# scheme.net
KiCad netlist of a schematic drawn in EAGLE
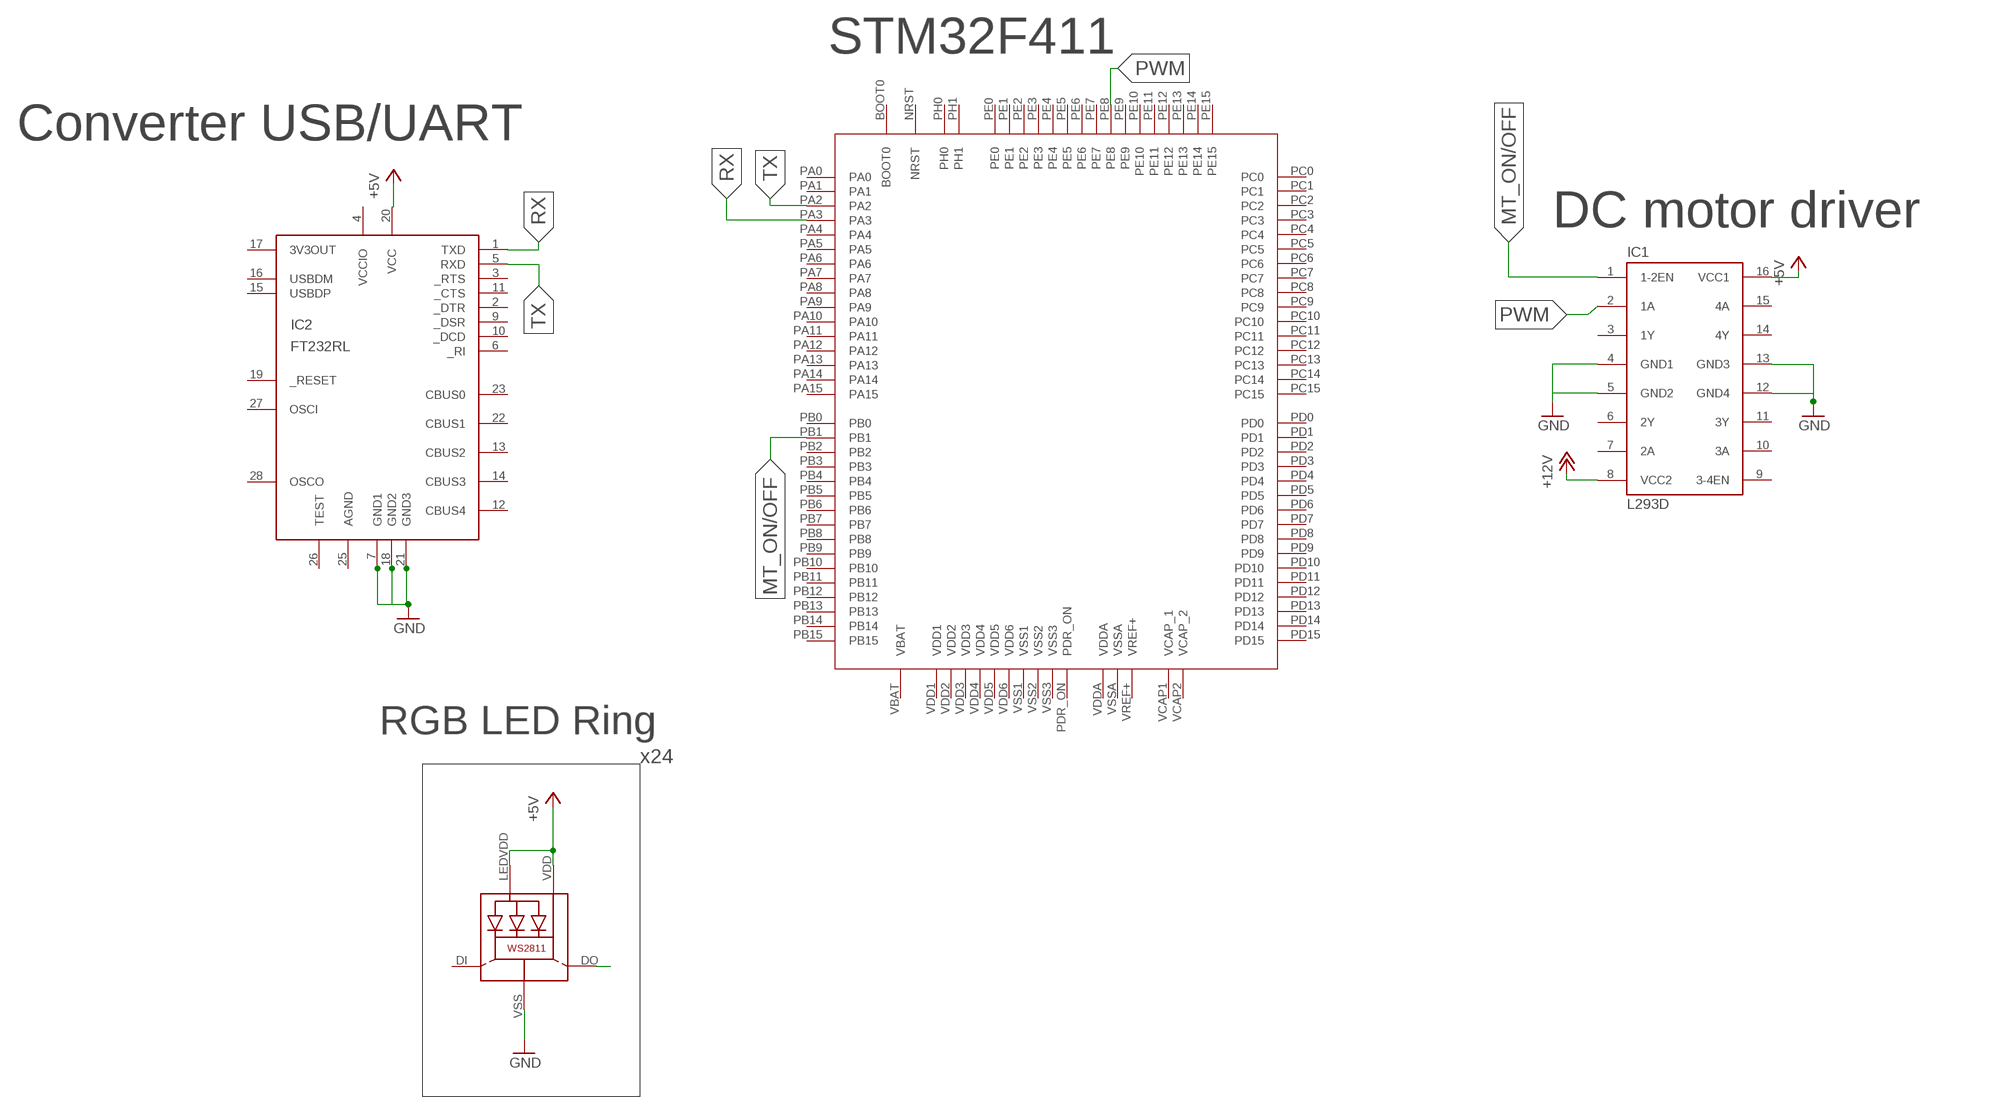
[diagram p0: schematic, sheet 1]

(export (version "E")
  (design (tool "Eeschema 10.0.6"))
  (components
    (comp (ref "IC1")
      (value "L293D")
      (footprint "eagle-import:DIL16")
      (libsource (lib "eagle-import") (part "L293D"))
    )
    (comp (ref "IC2")
      (value "FT232RL")
      (footprint "eagle-import:SSOP28DB")
      (libsource (lib "eagle-import") (part "FT232RL"))
    )
    (comp (ref "LED12")
      (value "WS28115050")
      (footprint "eagle-import:WS28115050")
      (libsource (lib "eagle-import") (part "WS28115050"))
    )
    (comp (ref "U$2")
      (value "STM32F4V_100PIN_GENERIC")
      (footprint "eagle-import:LQFP100")
      (libsource (lib "eagle-import") (part "STM32F4V_100PIN_GENERIC"))
    )
  )
  (nets
    (net (code "1") (name "+5V") (class "Default")
      (node (ref "IC1") (pin "16") (pinfunction "VCC1_16") (pintype "power_in"))
      (node (ref "IC2") (pin "20") (pinfunction "VCC_20") (pintype "power_in"))
      (node (ref "LED12") (pin "LEDVDD") (pinfunction "LEDVDD_LEDVDD") (pintype "power_in"))
      (node (ref "LED12") (pin "VDD") (pinfunction "VDD_VDD") (pintype "power_in"))
    )
    (net (code "2") (name "+12V") (class "Default")
      (node (ref "IC1") (pin "8") (pinfunction "VCC2_8") (pintype "power_in"))
    )
    (net (code "3") (name "/AGND") (class "Default")
      (node (ref "IC2") (pin "25") (pinfunction "AGND_25") (pintype "power_in"))
    )
    (net (code "4") (name "/VCCIO") (class "Default")
      (node (ref "IC2") (pin "4") (pinfunction "VCCIO_4") (pintype "power_in"))
    )
    (net (code "5") (name "GND") (class "Default")
      (node (ref "IC1") (pin "12") (pinfunction "GND4_12") (pintype "power_in"))
      (node (ref "IC1") (pin "13") (pinfunction "GND3_13") (pintype "power_in"))
      (node (ref "IC1") (pin "4") (pinfunction "GND1_4") (pintype "power_in"))
      (node (ref "IC1") (pin "5") (pinfunction "GND2_5") (pintype "power_in"))
      (node (ref "IC2") (pin "18") (pinfunction "GND2_18") (pintype "power_in"))
      (node (ref "IC2") (pin "21") (pinfunction "GND3_21") (pintype "power_in"))
      (node (ref "IC2") (pin "7") (pinfunction "GND1_7") (pintype "power_in"))
      (node (ref "LED12") (pin "VSS") (pinfunction "GND_VSS") (pintype "power_in"))
    )
    (net (code "6") (name "MT_ON{slash}OFF") (class "Default")
      (node (ref "IC1") (pin "1") (pinfunction "1-2EN_1") (pintype "input"))
      (node (ref "U$2") (pin "PB1") (pinfunction "PB1_PB1") (pintype "bidirectional"))
    )
    (net (code "7") (name "PWM") (class "Default")
      (node (ref "IC1") (pin "2") (pinfunction "1A_2") (pintype "input"))
      (node (ref "U$2") (pin "PE8") (pinfunction "PE8_PE8") (pintype "bidirectional"))
    )
    (net (code "8") (name "RX") (class "Default")
      (node (ref "IC2") (pin "1") (pinfunction "TXD_1") (pintype "output"))
      (node (ref "U$2") (pin "PA3") (pinfunction "PA3_PA3") (pintype "bidirectional"))
    )
    (net (code "9") (name "TX") (class "Default")
      (node (ref "IC2") (pin "5") (pinfunction "RXD_5") (pintype "input"))
      (node (ref "U$2") (pin "PA2") (pinfunction "PA2_PA2") (pintype "bidirectional"))
    )
    (net (code "10") (name "unconnected-(IC1-1Y-Pad3)") (class "Default")
      (node (ref "IC1") (pin "3") (pinfunction "1Y_3") (pintype "output"))
    )
    (net (code "11") (name "unconnected-(IC1-2A-Pad7)") (class "Default")
      (node (ref "IC1") (pin "7") (pinfunction "2A_7") (pintype "input"))
    )
    (net (code "12") (name "unconnected-(IC1-2Y-Pad6)") (class "Default")
      (node (ref "IC1") (pin "6") (pinfunction "2Y_6") (pintype "output"))
    )
    (net (code "13") (name "unconnected-(IC1-3-4EN-Pad9)") (class "Default")
      (node (ref "IC1") (pin "9") (pinfunction "3-4EN_9") (pintype "input"))
    )
    (net (code "14") (name "unconnected-(IC1-3A-Pad10)") (class "Default")
      (node (ref "IC1") (pin "10") (pinfunction "3A_10") (pintype "input"))
    )
    (net (code "15") (name "unconnected-(IC1-3Y-Pad11)") (class "Default")
      (node (ref "IC1") (pin "11") (pinfunction "3Y_11") (pintype "output"))
    )
    (net (code "16") (name "unconnected-(IC1-4A-Pad15)") (class "Default")
      (node (ref "IC1") (pin "15") (pinfunction "4A_15") (pintype "input"))
    )
    (net (code "17") (name "unconnected-(IC1-4Y-Pad14)") (class "Default")
      (node (ref "IC1") (pin "14") (pinfunction "4Y_14") (pintype "output"))
    )
    (net (code "18") (name "unconnected-(IC2-3V3OUT-Pad17)") (class "Default")
      (node (ref "IC2") (pin "17") (pinfunction "3V3OUT_17") (pintype "output"))
    )
    (net (code "19") (name "unconnected-(IC2-CBUS0-Pad23)") (class "Default")
      (node (ref "IC2") (pin "23") (pinfunction "CBUS0_23") (pintype "bidirectional"))
    )
    (net (code "20") (name "unconnected-(IC2-CBUS1-Pad22)") (class "Default")
      (node (ref "IC2") (pin "22") (pinfunction "CBUS1_22") (pintype "bidirectional"))
    )
    (net (code "21") (name "unconnected-(IC2-CBUS2-Pad13)") (class "Default")
      (node (ref "IC2") (pin "13") (pinfunction "CBUS2_13") (pintype "bidirectional"))
    )
    (net (code "22") (name "unconnected-(IC2-CBUS3-Pad14)") (class "Default")
      (node (ref "IC2") (pin "14") (pinfunction "CBUS3_14") (pintype "bidirectional"))
    )
    (net (code "23") (name "unconnected-(IC2-CBUS4-Pad12)") (class "Default")
      (node (ref "IC2") (pin "12") (pinfunction "CBUS4_12") (pintype "bidirectional"))
    )
    (net (code "24") (name "unconnected-(IC2-OSCI-Pad27)") (class "Default")
      (node (ref "IC2") (pin "27") (pinfunction "OSCI_27") (pintype "input"))
    )
    (net (code "25") (name "unconnected-(IC2-OSCO-Pad28)") (class "Default")
      (node (ref "IC2") (pin "28") (pinfunction "OSCO_28") (pintype "output"))
    )
    (net (code "26") (name "unconnected-(IC2-TEST-Pad26)") (class "Default")
      (node (ref "IC2") (pin "26") (pinfunction "TEST_26") (pintype "input"))
    )
    (net (code "27") (name "unconnected-(IC2-USBDM-Pad16)") (class "Default")
      (node (ref "IC2") (pin "16") (pinfunction "USBDM_16") (pintype "bidirectional"))
    )
    (net (code "28") (name "unconnected-(IC2-USBDP-Pad15)") (class "Default")
      (node (ref "IC2") (pin "15") (pinfunction "USBDP_15") (pintype "bidirectional"))
    )
    (net (code "29") (name "unconnected-(IC2-_CTS-Pad11)") (class "Default")
      (node (ref "IC2") (pin "11") (pinfunction "_CTS_11") (pintype "input"))
    )
    (net (code "30") (name "unconnected-(IC2-_DCD-Pad10)") (class "Default")
      (node (ref "IC2") (pin "10") (pinfunction "_DCD_10") (pintype "input"))
    )
    (net (code "31") (name "unconnected-(IC2-_DSR-Pad9)") (class "Default")
      (node (ref "IC2") (pin "9") (pinfunction "_DSR_9") (pintype "input"))
    )
    (net (code "32") (name "unconnected-(IC2-_DTR-Pad2)") (class "Default")
      (node (ref "IC2") (pin "2") (pinfunction "_DTR_2") (pintype "output"))
    )
    (net (code "33") (name "unconnected-(IC2-_RESET-Pad19)") (class "Default")
      (node (ref "IC2") (pin "19") (pinfunction "_RESET_19") (pintype "input"))
    )
    (net (code "34") (name "unconnected-(IC2-_RI-Pad6)") (class "Default")
      (node (ref "IC2") (pin "6") (pinfunction "_RI_6") (pintype "input"))
    )
    (net (code "35") (name "unconnected-(IC2-_RTS-Pad3)") (class "Default")
      (node (ref "IC2") (pin "3") (pinfunction "_RTS_3") (pintype "output"))
    )
    (net (code "36") (name "unconnected-(LED12-PadDI)") (class "Default")
      (node (ref "LED12") (pin "DI") (pinfunction "DI_DI") (pintype "input"))
    )
    (net (code "37") (name "unconnected-(LED12-PadDO)") (class "Default")
      (node (ref "LED12") (pin "DO") (pinfunction "DO_DO") (pintype "output"))
    )
    (net (code "38") (name "unconnected-(U$2-PadBOOT0)") (class "Default")
      (node (ref "U$2") (pin "BOOT0") (pinfunction "BOOT0_BOOT0") (pintype "bidirectional"))
    )
    (net (code "39") (name "unconnected-(U$2-PadNRST)") (class "Default")
      (node (ref "U$2") (pin "NRST") (pinfunction "NRST_NRST") (pintype "bidirectional"))
    )
    (net (code "40") (name "unconnected-(U$2-PadPA0)") (class "Default")
      (node (ref "U$2") (pin "PA0") (pinfunction "PA0_PA0") (pintype "bidirectional"))
    )
    (net (code "41") (name "unconnected-(U$2-PadPA1)") (class "Default")
      (node (ref "U$2") (pin "PA1") (pinfunction "PA1_PA1") (pintype "bidirectional"))
    )
    (net (code "42") (name "unconnected-(U$2-PadPA4)") (class "Default")
      (node (ref "U$2") (pin "PA4") (pinfunction "PA4_PA4") (pintype "bidirectional"))
    )
    (net (code "43") (name "unconnected-(U$2-PadPA5)") (class "Default")
      (node (ref "U$2") (pin "PA5") (pinfunction "PA5_PA5") (pintype "bidirectional"))
    )
    (net (code "44") (name "unconnected-(U$2-PadPA6)") (class "Default")
      (node (ref "U$2") (pin "PA6") (pinfunction "PA6_PA6") (pintype "bidirectional"))
    )
    (net (code "45") (name "unconnected-(U$2-PadPA7)") (class "Default")
      (node (ref "U$2") (pin "PA7") (pinfunction "PA7_PA7") (pintype "bidirectional"))
    )
    (net (code "46") (name "unconnected-(U$2-PadPA8)") (class "Default")
      (node (ref "U$2") (pin "PA8") (pinfunction "PA8_PA8") (pintype "bidirectional"))
    )
    (net (code "47") (name "unconnected-(U$2-PadPA9)") (class "Default")
      (node (ref "U$2") (pin "PA9") (pinfunction "PA9_PA9") (pintype "bidirectional"))
    )
    (net (code "48") (name "unconnected-(U$2-PadPA10)") (class "Default")
      (node (ref "U$2") (pin "PA10") (pinfunction "PA10_PA10") (pintype "bidirectional"))
    )
    (net (code "49") (name "unconnected-(U$2-PadPA11)") (class "Default")
      (node (ref "U$2") (pin "PA11") (pinfunction "PA11_PA11") (pintype "bidirectional"))
    )
    (net (code "50") (name "unconnected-(U$2-PadPA12)") (class "Default")
      (node (ref "U$2") (pin "PA12") (pinfunction "PA12_PA12") (pintype "bidirectional"))
    )
    (net (code "51") (name "unconnected-(U$2-PadPA13)") (class "Default")
      (node (ref "U$2") (pin "PA13") (pinfunction "PA13_PA13") (pintype "bidirectional"))
    )
    (net (code "52") (name "unconnected-(U$2-PadPA14)") (class "Default")
      (node (ref "U$2") (pin "PA14") (pinfunction "PA14_PA14") (pintype "bidirectional"))
    )
    (net (code "53") (name "unconnected-(U$2-PadPA15)") (class "Default")
      (node (ref "U$2") (pin "PA15") (pinfunction "PA15_PA15") (pintype "bidirectional"))
    )
    (net (code "54") (name "unconnected-(U$2-PadPB0)") (class "Default")
      (node (ref "U$2") (pin "PB0") (pinfunction "PB0_PB0") (pintype "bidirectional"))
    )
    (net (code "55") (name "unconnected-(U$2-PadPB2)") (class "Default")
      (node (ref "U$2") (pin "PB2") (pinfunction "PB2_PB2") (pintype "bidirectional"))
    )
    (net (code "56") (name "unconnected-(U$2-PadPB3)") (class "Default")
      (node (ref "U$2") (pin "PB3") (pinfunction "PB3_PB3") (pintype "bidirectional"))
    )
    (net (code "57") (name "unconnected-(U$2-PadPB4)") (class "Default")
      (node (ref "U$2") (pin "PB4") (pinfunction "PB4_PB4") (pintype "bidirectional"))
    )
    (net (code "58") (name "unconnected-(U$2-PadPB5)") (class "Default")
      (node (ref "U$2") (pin "PB5") (pinfunction "PB5_PB5") (pintype "bidirectional"))
    )
    (net (code "59") (name "unconnected-(U$2-PadPB6)") (class "Default")
      (node (ref "U$2") (pin "PB6") (pinfunction "PB6_PB6") (pintype "bidirectional"))
    )
    (net (code "60") (name "unconnected-(U$2-PadPB7)") (class "Default")
      (node (ref "U$2") (pin "PB7") (pinfunction "PB7_PB7") (pintype "bidirectional"))
    )
    (net (code "61") (name "unconnected-(U$2-PadPB8)") (class "Default")
      (node (ref "U$2") (pin "PB8") (pinfunction "PB8_PB8") (pintype "bidirectional"))
    )
    (net (code "62") (name "unconnected-(U$2-PadPB9)") (class "Default")
      (node (ref "U$2") (pin "PB9") (pinfunction "PB9_PB9") (pintype "bidirectional"))
    )
    (net (code "63") (name "unconnected-(U$2-PadPB10)") (class "Default")
      (node (ref "U$2") (pin "PB10") (pinfunction "PB10_PB10") (pintype "bidirectional"))
    )
    (net (code "64") (name "unconnected-(U$2-PadPB11)") (class "Default")
      (node (ref "U$2") (pin "PB11") (pinfunction "PB11_PB11") (pintype "bidirectional"))
    )
    (net (code "65") (name "unconnected-(U$2-PadPB12)") (class "Default")
      (node (ref "U$2") (pin "PB12") (pinfunction "PB12_PB12") (pintype "bidirectional"))
    )
    (net (code "66") (name "unconnected-(U$2-PadPB13)") (class "Default")
      (node (ref "U$2") (pin "PB13") (pinfunction "PB13_PB13") (pintype "bidirectional"))
    )
    (net (code "67") (name "unconnected-(U$2-PadPB14)") (class "Default")
      (node (ref "U$2") (pin "PB14") (pinfunction "PB14_PB14") (pintype "bidirectional"))
    )
    (net (code "68") (name "unconnected-(U$2-PadPB15)") (class "Default")
      (node (ref "U$2") (pin "PB15") (pinfunction "PB15_PB15") (pintype "bidirectional"))
    )
    (net (code "69") (name "unconnected-(U$2-PadPC0)") (class "Default")
      (node (ref "U$2") (pin "PC0") (pinfunction "PC0_PC0") (pintype "bidirectional"))
    )
    (net (code "70") (name "unconnected-(U$2-PadPC1)") (class "Default")
      (node (ref "U$2") (pin "PC1") (pinfunction "PC1_PC1") (pintype "bidirectional"))
    )
    (net (code "71") (name "unconnected-(U$2-PadPC2)") (class "Default")
      (node (ref "U$2") (pin "PC2") (pinfunction "PC2_PC2") (pintype "bidirectional"))
    )
    (net (code "72") (name "unconnected-(U$2-PadPC3)") (class "Default")
      (node (ref "U$2") (pin "PC3") (pinfunction "PC3_PC3") (pintype "bidirectional"))
    )
    (net (code "73") (name "unconnected-(U$2-PadPC4)") (class "Default")
      (node (ref "U$2") (pin "PC4") (pinfunction "PC4_PC4") (pintype "bidirectional"))
    )
    (net (code "74") (name "unconnected-(U$2-PadPC5)") (class "Default")
      (node (ref "U$2") (pin "PC5") (pinfunction "PC5_PC5") (pintype "bidirectional"))
    )
    (net (code "75") (name "unconnected-(U$2-PadPC6)") (class "Default")
      (node (ref "U$2") (pin "PC6") (pinfunction "PC6_PC6") (pintype "bidirectional"))
    )
    (net (code "76") (name "unconnected-(U$2-PadPC7)") (class "Default")
      (node (ref "U$2") (pin "PC7") (pinfunction "PC7_PC7") (pintype "bidirectional"))
    )
    (net (code "77") (name "unconnected-(U$2-PadPC8)") (class "Default")
      (node (ref "U$2") (pin "PC8") (pinfunction "PC8_PC8") (pintype "bidirectional"))
    )
    (net (code "78") (name "unconnected-(U$2-PadPC9)") (class "Default")
      (node (ref "U$2") (pin "PC9") (pinfunction "PC9_PC9") (pintype "bidirectional"))
    )
    (net (code "79") (name "unconnected-(U$2-PadPC10)") (class "Default")
      (node (ref "U$2") (pin "PC10") (pinfunction "PC10_PC10") (pintype "bidirectional"))
    )
    (net (code "80") (name "unconnected-(U$2-PadPC11)") (class "Default")
      (node (ref "U$2") (pin "PC11") (pinfunction "PC11_PC11") (pintype "bidirectional"))
    )
    (net (code "81") (name "unconnected-(U$2-PadPC12)") (class "Default")
      (node (ref "U$2") (pin "PC12") (pinfunction "PC12_PC12") (pintype "bidirectional"))
    )
    (net (code "82") (name "unconnected-(U$2-PadPC13)") (class "Default")
      (node (ref "U$2") (pin "PC13") (pinfunction "PC13_PC13") (pintype "bidirectional"))
    )
    (net (code "83") (name "unconnected-(U$2-PadPC14)") (class "Default")
      (node (ref "U$2") (pin "PC14") (pinfunction "PC14_PC14") (pintype "bidirectional"))
    )
    (net (code "84") (name "unconnected-(U$2-PadPC15)") (class "Default")
      (node (ref "U$2") (pin "PC15") (pinfunction "PC15_PC15") (pintype "bidirectional"))
    )
    (net (code "85") (name "unconnected-(U$2-PadPD0)") (class "Default")
      (node (ref "U$2") (pin "PD0") (pinfunction "PD0_PD0") (pintype "bidirectional"))
    )
    (net (code "86") (name "unconnected-(U$2-PadPD1)") (class "Default")
      (node (ref "U$2") (pin "PD1") (pinfunction "PD1_PD1") (pintype "bidirectional"))
    )
    (net (code "87") (name "unconnected-(U$2-PadPD2)") (class "Default")
      (node (ref "U$2") (pin "PD2") (pinfunction "PD2_PD2") (pintype "bidirectional"))
    )
    (net (code "88") (name "unconnected-(U$2-PadPD3)") (class "Default")
      (node (ref "U$2") (pin "PD3") (pinfunction "PD3_PD3") (pintype "bidirectional"))
    )
    (net (code "89") (name "unconnected-(U$2-PadPD4)") (class "Default")
      (node (ref "U$2") (pin "PD4") (pinfunction "PD4_PD4") (pintype "bidirectional"))
    )
    (net (code "90") (name "unconnected-(U$2-PadPD5)") (class "Default")
      (node (ref "U$2") (pin "PD5") (pinfunction "PD5_PD5") (pintype "bidirectional"))
    )
    (net (code "91") (name "unconnected-(U$2-PadPD6)") (class "Default")
      (node (ref "U$2") (pin "PD6") (pinfunction "PD6_PD6") (pintype "bidirectional"))
    )
    (net (code "92") (name "unconnected-(U$2-PadPD7)") (class "Default")
      (node (ref "U$2") (pin "PD7") (pinfunction "PD7_PD7") (pintype "bidirectional"))
    )
    (net (code "93") (name "unconnected-(U$2-PadPD8)") (class "Default")
      (node (ref "U$2") (pin "PD8") (pinfunction "PD8_PD8") (pintype "bidirectional"))
    )
    (net (code "94") (name "unconnected-(U$2-PadPD9)") (class "Default")
      (node (ref "U$2") (pin "PD9") (pinfunction "PD9_PD9") (pintype "bidirectional"))
    )
    (net (code "95") (name "unconnected-(U$2-PadPD10)") (class "Default")
      (node (ref "U$2") (pin "PD10") (pinfunction "PD10_PD10") (pintype "bidirectional"))
    )
    (net (code "96") (name "unconnected-(U$2-PadPD11)") (class "Default")
      (node (ref "U$2") (pin "PD11") (pinfunction "PD11_PD11") (pintype "bidirectional"))
    )
    (net (code "97") (name "unconnected-(U$2-PadPD12)") (class "Default")
      (node (ref "U$2") (pin "PD12") (pinfunction "PD12_PD12") (pintype "bidirectional"))
    )
    (net (code "98") (name "unconnected-(U$2-PadPD13)") (class "Default")
      (node (ref "U$2") (pin "PD13") (pinfunction "PD13_PD13") (pintype "bidirectional"))
    )
    (net (code "99") (name "unconnected-(U$2-PadPD14)") (class "Default")
      (node (ref "U$2") (pin "PD14") (pinfunction "PD14_PD14") (pintype "bidirectional"))
    )
    (net (code "100") (name "unconnected-(U$2-PadPD15)") (class "Default")
      (node (ref "U$2") (pin "PD15") (pinfunction "PD15_PD15") (pintype "bidirectional"))
    )
    (net (code "101") (name "unconnected-(U$2-PadPDR_ON)") (class "Default")
      (node (ref "U$2") (pin "PDR_ON") (pinfunction "PDR_ON_PDR_ON") (pintype "bidirectional"))
    )
    (net (code "102") (name "unconnected-(U$2-PadPE0)") (class "Default")
      (node (ref "U$2") (pin "PE0") (pinfunction "PE0_PE0") (pintype "bidirectional"))
    )
    (net (code "103") (name "unconnected-(U$2-PadPE1)") (class "Default")
      (node (ref "U$2") (pin "PE1") (pinfunction "PE1_PE1") (pintype "bidirectional"))
    )
    (net (code "104") (name "unconnected-(U$2-PadPE2)") (class "Default")
      (node (ref "U$2") (pin "PE2") (pinfunction "PE2_PE2") (pintype "bidirectional"))
    )
    (net (code "105") (name "unconnected-(U$2-PadPE3)") (class "Default")
      (node (ref "U$2") (pin "PE3") (pinfunction "PE3_PE3") (pintype "bidirectional"))
    )
    (net (code "106") (name "unconnected-(U$2-PadPE4)") (class "Default")
      (node (ref "U$2") (pin "PE4") (pinfunction "PE4_PE4") (pintype "bidirectional"))
    )
    (net (code "107") (name "unconnected-(U$2-PadPE5)") (class "Default")
      (node (ref "U$2") (pin "PE5") (pinfunction "PE5_PE5") (pintype "bidirectional"))
    )
    (net (code "108") (name "unconnected-(U$2-PadPE6)") (class "Default")
      (node (ref "U$2") (pin "PE6") (pinfunction "PE6_PE6") (pintype "bidirectional"))
    )
    (net (code "109") (name "unconnected-(U$2-PadPE7)") (class "Default")
      (node (ref "U$2") (pin "PE7") (pinfunction "PE7_PE7") (pintype "bidirectional"))
    )
    (net (code "110") (name "unconnected-(U$2-PadPE9)") (class "Default")
      (node (ref "U$2") (pin "PE9") (pinfunction "PE9_PE9") (pintype "bidirectional"))
    )
    (net (code "111") (name "unconnected-(U$2-PadPE10)") (class "Default")
      (node (ref "U$2") (pin "PE10") (pinfunction "PE10_PE10") (pintype "bidirectional"))
    )
    (net (code "112") (name "unconnected-(U$2-PadPE11)") (class "Default")
      (node (ref "U$2") (pin "PE11") (pinfunction "PE11_PE11") (pintype "bidirectional"))
    )
    (net (code "113") (name "unconnected-(U$2-PadPE12)") (class "Default")
      (node (ref "U$2") (pin "PE12") (pinfunction "PE12_PE12") (pintype "bidirectional"))
    )
    (net (code "114") (name "unconnected-(U$2-PadPE13)") (class "Default")
      (node (ref "U$2") (pin "PE13") (pinfunction "PE13_PE13") (pintype "bidirectional"))
    )
    (net (code "115") (name "unconnected-(U$2-PadPE14)") (class "Default")
      (node (ref "U$2") (pin "PE14") (pinfunction "PE14_PE14") (pintype "bidirectional"))
    )
    (net (code "116") (name "unconnected-(U$2-PadPE15)") (class "Default")
      (node (ref "U$2") (pin "PE15") (pinfunction "PE15_PE15") (pintype "bidirectional"))
    )
    (net (code "117") (name "unconnected-(U$2-PadPH0)") (class "Default")
      (node (ref "U$2") (pin "PH0") (pinfunction "PH0_PH0") (pintype "bidirectional"))
    )
    (net (code "118") (name "unconnected-(U$2-PadPH1)") (class "Default")
      (node (ref "U$2") (pin "PH1") (pinfunction "PH1_PH1") (pintype "bidirectional"))
    )
    (net (code "119") (name "unconnected-(U$2-PadVBAT)") (class "Default")
      (node (ref "U$2") (pin "VBAT") (pinfunction "VBAT_VBAT") (pintype "bidirectional"))
    )
    (net (code "120") (name "unconnected-(U$2-PadVDD1)") (class "Default")
      (node (ref "U$2") (pin "VDD1") (pinfunction "VDD1_VDD1") (pintype "bidirectional"))
    )
    (net (code "121") (name "unconnected-(U$2-PadVDD2)") (class "Default")
      (node (ref "U$2") (pin "VDD2") (pinfunction "VDD2_VDD2") (pintype "bidirectional"))
    )
    (net (code "122") (name "unconnected-(U$2-PadVDD3)") (class "Default")
      (node (ref "U$2") (pin "VDD3") (pinfunction "VDD3_VDD3") (pintype "bidirectional"))
    )
    (net (code "123") (name "unconnected-(U$2-PadVDD4)") (class "Default")
      (node (ref "U$2") (pin "VDD4") (pinfunction "VDD4_VDD4") (pintype "bidirectional"))
    )
    (net (code "124") (name "unconnected-(U$2-PadVDD5)") (class "Default")
      (node (ref "U$2") (pin "VDD5") (pinfunction "VDD5_VDD5") (pintype "bidirectional"))
    )
    (net (code "125") (name "unconnected-(U$2-PadVDD6)") (class "Default")
      (node (ref "U$2") (pin "VDD6") (pinfunction "VDD6_VDD6") (pintype "bidirectional"))
    )
    (net (code "126") (name "unconnected-(U$2-PadVDDA)") (class "Default")
      (node (ref "U$2") (pin "VDDA") (pinfunction "VDDA_VDDA") (pintype "bidirectional"))
    )
    (net (code "127") (name "unconnected-(U$2-PadVREF+)") (class "Default")
      (node (ref "U$2") (pin "VREF+") (pinfunction "VREF+_VREF+") (pintype "bidirectional"))
    )
    (net (code "128") (name "unconnected-(U$2-PadVSS1)") (class "Default")
      (node (ref "U$2") (pin "VSS1") (pinfunction "VSS1_VSS1") (pintype "bidirectional"))
    )
    (net (code "129") (name "unconnected-(U$2-PadVSS2)") (class "Default")
      (node (ref "U$2") (pin "VSS2") (pinfunction "VSS2_VSS2") (pintype "bidirectional"))
    )
    (net (code "130") (name "unconnected-(U$2-PadVSS3)") (class "Default")
      (node (ref "U$2") (pin "VSS3") (pinfunction "VSS3_VSS3") (pintype "bidirectional"))
    )
    (net (code "131") (name "unconnected-(U$2-PadVSSA)") (class "Default")
      (node (ref "U$2") (pin "VSSA") (pinfunction "VSSA_VSSA") (pintype "bidirectional"))
    )
    (net (code "132") (name "unconnected-(U$2-VCAP_1-PadVCAP1)") (class "Default")
      (node (ref "U$2") (pin "VCAP1") (pinfunction "VCAP_1_VCAP1") (pintype "bidirectional"))
    )
    (net (code "133") (name "unconnected-(U$2-VCAP_2-PadVCAP2)") (class "Default")
      (node (ref "U$2") (pin "VCAP2") (pinfunction "VCAP_2_VCAP2") (pintype "bidirectional"))
    )
  )
)
